# Assistant_Parameters.net
KiCad netlist of a schematic drawn in Altium Designer
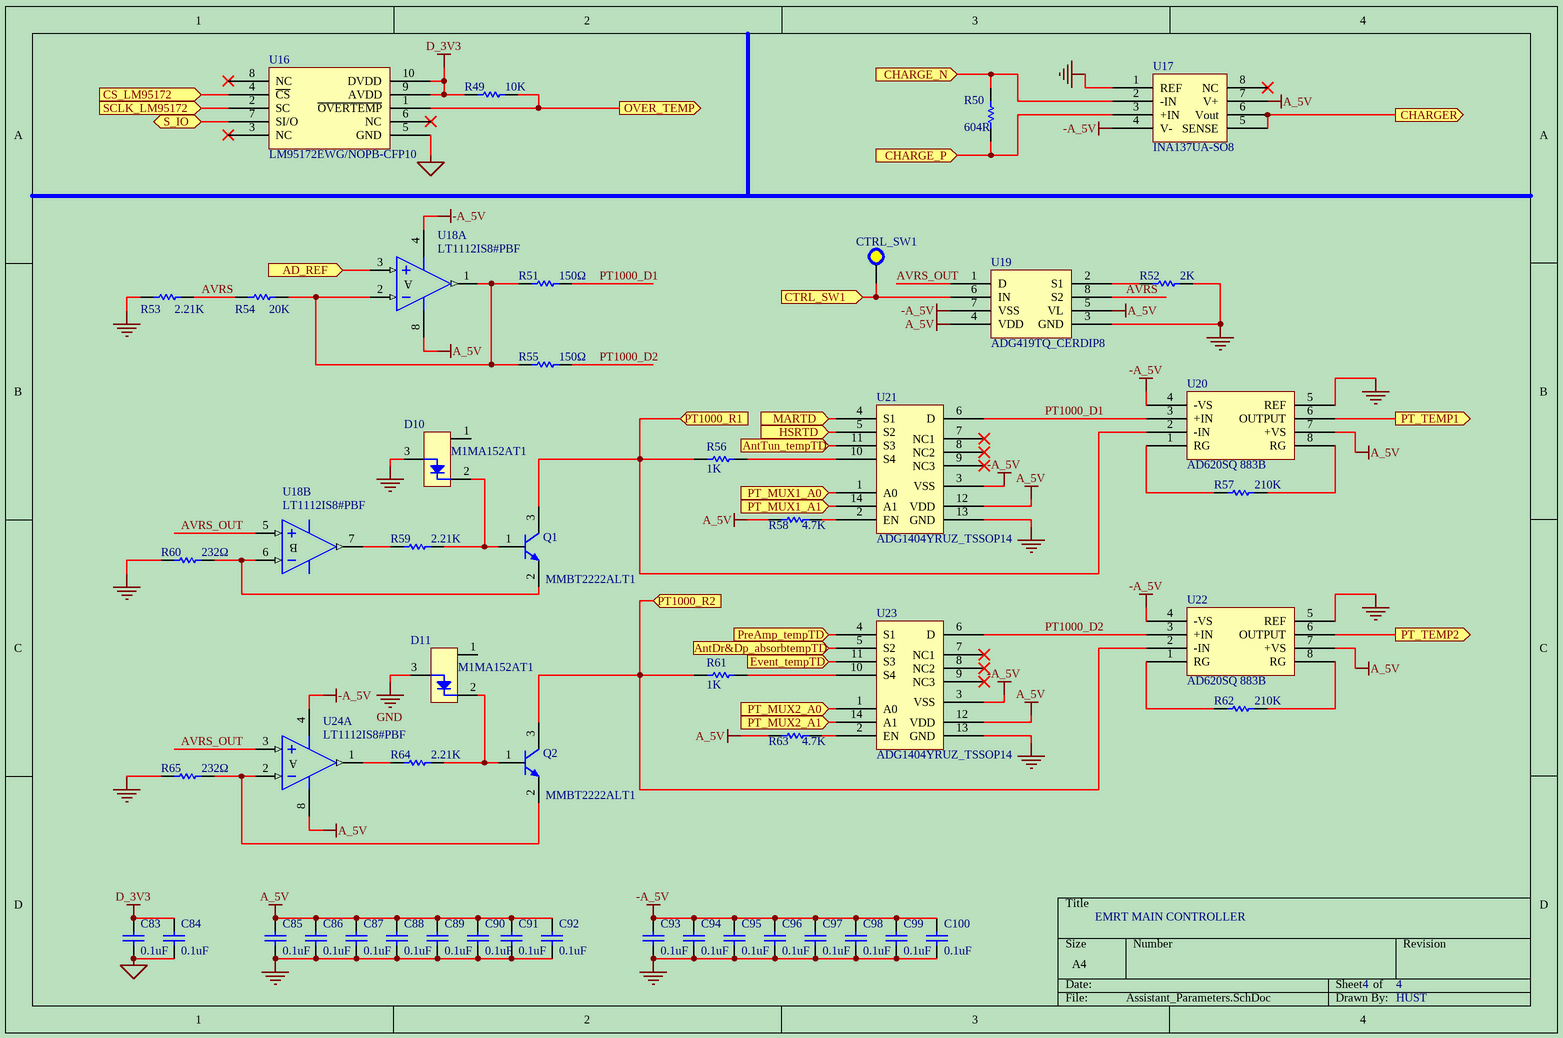
[diagram p0: Assistant_Parameters.SchDoc]

(export (version "E")
  (design (tool "Eeschema 10.0.6"))
  (components
    (comp (ref "C83")
      (value "0.1uF")
      (footprint "CAPS0805_57")
      (description "Capacitor")
      (fields (field (name "PART NUMBER") "Y20025084") (field (name "Comment") "Cap"))
      (libsource (lib "Cap") (part "Cap"))
    )
    (comp (ref "C84")
      (value "0.1uF")
      (footprint "CAPS0805_57")
      (description "Capacitor")
      (fields (field (name "PART NUMBER") "Y20025084") (field (name "Comment") "Cap"))
      (libsource (lib "Cap") (part "Cap"))
    )
    (comp (ref "C85")
      (value "0.1uF")
      (footprint "CAPS0805_57")
      (description "Capacitor")
      (fields (field (name "PART NUMBER") "Y20024100") (field (name "Comment") "Cap"))
      (libsource (lib "电容") (part "Y20024100"))
    )
    (comp (ref "C86")
      (value "Cap")
      (footprint "CAPS0805_57")
      (description "Capacitor")
      (fields (field (name "PART NUMBER") "Y20002409") (field (name "ALTIUM_UNNAMED_8") "0.1uF"))
      (libsource (lib "电容") (part "Y20002409"))
    )
    (comp (ref "C87")
      (value "0.1uF")
      (footprint "CAPS0805_57")
      (description "Capacitor")
      (fields (field (name "PART NUMBER") "Y20025084") (field (name "Comment") "Cap"))
      (libsource (lib "Cap") (part "Cap"))
    )
    (comp (ref "C88")
      (value "0.1uF")
      (footprint "CAPS0805_57")
      (description "Capacitor")
      (fields (field (name "PART NUMBER") "Y20024100") (field (name "Comment") "Cap"))
      (libsource (lib "电容") (part "Y20024100"))
    )
    (comp (ref "C89")
      (value "0.1uF")
      (footprint "CAPS0805_57")
      (description "Capacitor")
      (fields (field (name "PART NUMBER") "Y20024100") (field (name "Comment") "Cap"))
      (libsource (lib "电容") (part "Y20024100"))
    )
    (comp (ref "C90")
      (value "0.1uF")
      (footprint "CAPS0805_57")
      (description "Capacitor")
      (fields (field (name "PART NUMBER") "Y20024100") (field (name "Comment") "Cap"))
      (libsource (lib "电容") (part "Y20024100"))
    )
    (comp (ref "C91")
      (value "0.1uF")
      (footprint "CAPS0805_57")
      (description "Capacitor")
      (fields (field (name "PART NUMBER") "Y20024100") (field (name "Comment") "Cap"))
      (libsource (lib "电容") (part "Y20024100"))
    )
    (comp (ref "C92")
      (value "0.1uF")
      (footprint "CAPS0805_57")
      (description "Capacitor")
      (fields (field (name "PART NUMBER") "Y20024100") (field (name "Comment") "Cap"))
      (libsource (lib "电容") (part "Y20024100"))
    )
    (comp (ref "C93")
      (value "0.1uF")
      (footprint "CAPS0805_57")
      (description "Capacitor")
      (fields (field (name "PART NUMBER") "Y20025084") (field (name "Comment") "Cap"))
      (libsource (lib "Cap") (part "Cap"))
    )
    (comp (ref "C94")
      (value "Cap")
      (footprint "CAPS0805_57")
      (description "Capacitor")
      (fields (field (name "PART NUMBER") "Y20002409") (field (name "ALTIUM_UNNAMED_8") "0.1uF"))
      (libsource (lib "电容") (part "Y20002409"))
    )
    (comp (ref "C95")
      (value "0.1uF")
      (footprint "CAPS0805_57")
      (description "Capacitor")
      (fields (field (name "PART NUMBER") "Y20024100") (field (name "Comment") "Cap"))
      (libsource (lib "电容") (part "Y20024100"))
    )
    (comp (ref "C96")
      (value "0.1uF")
      (footprint "CAPS0805_57")
      (description "Capacitor")
      (fields (field (name "PART NUMBER") "Y20024100") (field (name "Comment") "Cap"))
      (libsource (lib "电容") (part "Y20024100"))
    )
    (comp (ref "C97")
      (value "0.1uF")
      (footprint "CAPS0805_57")
      (description "Capacitor")
      (fields (field (name "PART NUMBER") "Y20024100") (field (name "Comment") "Cap"))
      (libsource (lib "电容") (part "Y20024100"))
    )
    (comp (ref "C98")
      (value "0.1uF")
      (footprint "CAPS0805_57")
      (description "Capacitor")
      (fields (field (name "PART NUMBER") "Y20024100") (field (name "Comment") "Cap"))
      (libsource (lib "电容") (part "Y20024100"))
    )
    (comp (ref "C99")
      (value "0.1uF")
      (footprint "CAPS0805_57")
      (description "Capacitor")
      (fields (field (name "PART NUMBER") "Y20024100") (field (name "Comment") "Cap"))
      (libsource (lib "电容") (part "Y20024100"))
    )
    (comp (ref "C100")
      (value "0.1uF")
      (footprint "CAPS0805_57")
      (description "Capacitor")
      (fields (field (name "PART NUMBER") "Y20024100") (field (name "Comment") "Cap"))
      (libsource (lib "电容") (part "Y20024100"))
    )
    (comp (ref "CTRL_SW1")
      (value "TEST_SMALL")
      (footprint "test_small")
      (libsource (lib "srj") (part "TEST_SMALL"))
    )
    (comp (ref "D10")
      (value "M1MA152AT1")
      (footprint "SC-59")
      (fields (field (name "PART NUMBER") "Y20032999"))
      (libsource (lib "MC-HT") (part "M1MA152AT1"))
    )
    (comp (ref "D11")
      (value "M1MA152AT1")
      (footprint "SC-59")
      (fields (field (name "PART NUMBER") "Y20032999"))
      (libsource (lib "MC-HT") (part "M1MA152AT1"))
    )
    (comp (ref "Q1")
      (value "MMBT2222ALT1")
      (footprint "V-PDSO_3q290×240×100_p190")
      (description "General Purpose Transistor NPN Silicon")
      (libsource (lib "MC-HT") (part "MMBT2222ALT1"))
    )
    (comp (ref "Q2")
      (value "MMBT2222ALT1")
      (footprint "V-PDSO_3q290×240×100_p190")
      (description "General Purpose Transistor NPN Silicon")
      (libsource (lib "MC-HT") (part "MMBT2222ALT1"))
    )
    (comp (ref "R49")
      (value "10K")
      (footprint "RESS0805")
      (description "Semiconductor Resistor")
      (fields
        (field (name "MANUFACTURER") "Generic Components")
        (field (name "Comment") "Res")
        (field (name "PUBLISHER") "Altium Hobart Technology Centre")
      )
      (libsource (lib "EMRT MAIN CONTROLLER") (part "Res"))
    )
    (comp (ref "R50")
      (value "604R")
      (footprint "RESS0805")
      (description "Semiconductor Resistor")
      (fields
        (field (name "MANUFACTURER") "Generic Components")
        (field (name "Comment") "Res")
        (field (name "PUBLISHER") "Altium Hobart Technology Centre")
      )
      (libsource (lib "EMRT MAIN CONTROLLER") (part "Res"))
    )
    (comp (ref "R51")
      (value "150Ω")
      (footprint "RESS0805")
      (description "Semiconductor Resistor")
      (fields
        (field (name "MANUFACTURER") "Generic Components")
        (field (name "Comment") "Res")
        (field (name "PUBLISHER") "Altium Hobart Technology Centre")
      )
      (libsource (lib "EMRT MAIN CONTROLLER") (part "Res"))
    )
    (comp (ref "R52")
      (value "2K")
      (footprint "RESS0805")
      (description "Semiconductor Resistor")
      (fields
        (field (name "MANUFACTURER") "Generic Components")
        (field (name "Comment") "Res")
        (field (name "PUBLISHER") "Altium Hobart Technology Centre")
      )
      (libsource (lib "EMRT MAIN CONTROLLER") (part "Res"))
    )
    (comp (ref "R53")
      (value "2.21K")
      (footprint "RESS0805")
      (description "Semiconductor Resistor")
      (fields
        (field (name "MANUFACTURER") "Generic Components")
        (field (name "Comment") "Res")
        (field (name "PUBLISHER") "Altium Hobart Technology Centre")
      )
      (libsource (lib "EMRT MAIN CONTROLLER") (part "Res"))
    )
    (comp (ref "R54")
      (value "20K")
      (footprint "EMRT MAIN CONTROLLER:RESS0805")
      (description "Semiconductor Resistor")
      (fields
        (field (name "MANUFACTURER") "Generic Components")
        (field (name "Comment") "Res")
        (field (name "PUBLISHER") "Altium Hobart Technology Centre")
      )
      (libsource (lib "EMRT MAIN CONTROLLER") (part "Res"))
    )
    (comp (ref "R55")
      (value "150Ω")
      (footprint "RESS0805")
      (description "Semiconductor Resistor")
      (fields
        (field (name "MANUFACTURER") "Generic Components")
        (field (name "Comment") "Res")
        (field (name "PUBLISHER") "Altium Hobart Technology Centre")
      )
      (libsource (lib "EMRT MAIN CONTROLLER") (part "Res"))
    )
    (comp (ref "R56")
      (value "1K")
      (footprint "RESS0805")
      (description "Semiconductor Resistor")
      (fields
        (field (name "MANUFACTURER") "Generic Components")
        (field (name "Comment") "Res")
        (field (name "PUBLISHER") "Altium Hobart Technology Centre")
      )
      (libsource (lib "EMRT MAIN CONTROLLER") (part "Res"))
    )
    (comp (ref "R57")
      (value "210K")
      (footprint "RESS0805")
      (description "Semiconductor Resistor")
      (fields
        (field (name "MANUFACTURER") "Generic Components")
        (field (name "Comment") "Res")
        (field (name "PUBLISHER") "Altium Hobart Technology Centre")
      )
      (libsource (lib "EMRT MAIN CONTROLLER") (part "Res"))
    )
    (comp (ref "R58")
      (value "4.7K")
      (footprint "RESS0805")
      (description "Semiconductor Resistor")
      (fields
        (field (name "MANUFACTURER") "Generic Components")
        (field (name "Comment") "Res")
        (field (name "PUBLISHER") "Altium Hobart Technology Centre")
      )
      (libsource (lib "EMRT MAIN CONTROLLER") (part "Res"))
    )
    (comp (ref "R59")
      (value "2.21K")
      (footprint "RESS0805")
      (description "Semiconductor Resistor")
      (fields
        (field (name "MANUFACTURER") "Generic Components")
        (field (name "Comment") "Res")
        (field (name "PUBLISHER") "Altium Hobart Technology Centre")
      )
      (libsource (lib "EMRT MAIN CONTROLLER") (part "Res"))
    )
    (comp (ref "R60")
      (value "232Ω")
      (footprint "RESS0805")
      (description "Semiconductor Resistor")
      (fields
        (field (name "MANUFACTURER") "Generic Components")
        (field (name "Comment") "Res")
        (field (name "PUBLISHER") "Altium Hobart Technology Centre")
      )
      (libsource (lib "EMRT MAIN CONTROLLER") (part "Res"))
    )
    (comp (ref "R61")
      (value "1K")
      (footprint "RESS0805")
      (description "Semiconductor Resistor")
      (fields
        (field (name "MANUFACTURER") "Generic Components")
        (field (name "Comment") "Res")
        (field (name "PUBLISHER") "Altium Hobart Technology Centre")
      )
      (libsource (lib "EMRT MAIN CONTROLLER") (part "Res"))
    )
    (comp (ref "R62")
      (value "210K")
      (footprint "RESS0805")
      (description "Semiconductor Resistor")
      (fields
        (field (name "MANUFACTURER") "Generic Components")
        (field (name "Comment") "Res")
        (field (name "PUBLISHER") "Altium Hobart Technology Centre")
      )
      (libsource (lib "EMRT MAIN CONTROLLER") (part "Res"))
    )
    (comp (ref "R63")
      (value "4.7K")
      (footprint "RESS0805")
      (description "Semiconductor Resistor")
      (fields
        (field (name "MANUFACTURER") "Generic Components")
        (field (name "Comment") "Res")
        (field (name "PUBLISHER") "Altium Hobart Technology Centre")
      )
      (libsource (lib "EMRT MAIN CONTROLLER") (part "Res"))
    )
    (comp (ref "R64")
      (value "2.21K")
      (footprint "RESS0805")
      (description "Semiconductor Resistor")
      (fields
        (field (name "MANUFACTURER") "Generic Components")
        (field (name "Comment") "Res")
        (field (name "PUBLISHER") "Altium Hobart Technology Centre")
      )
      (libsource (lib "EMRT MAIN CONTROLLER") (part "Res"))
    )
    (comp (ref "R65")
      (value "232Ω")
      (footprint "RESS0805")
      (description "Semiconductor Resistor")
      (fields
        (field (name "MANUFACTURER") "Generic Components")
        (field (name "Comment") "Res")
        (field (name "PUBLISHER") "Altium Hobart Technology Centre")
      )
      (libsource (lib "EMRT MAIN CONTROLLER") (part "Res"))
    )
    (comp (ref "U16")
      (value "LM95172EWG/NOPB-CFP10")
      (footprint "SOP10")
      (libsource (lib "srj") (part "LM95172EWG/NOPB"))
    )
    (comp (ref "U17")
      (value "INA137UA-SO8")
      (footprint "PDSO_8q600×490×175_p127")
      (libsource (lib "srj") (part "INA137"))
    )
    (comp (ref "U18")
      (value "LT1112IS8#PBF")
      (footprint "PDSO_8q600×490×175_p127")
      (description "Precision, Single-Supply Dual Operational Amplifier")
      (libsource (lib "MC-HT") (part "LT1112IS8#PBF"))
    )
    (comp (ref "U19")
      (value "ADG419TQ_CERDIP8")
      (footprint "CDIP_8q405×305×200_d19_p100_i300")
      (libsource (lib "MC-HT") (part "ADG419TQ/883"))
    )
    (comp (ref "U20")
      (value "AD620SQ 883B")
      (footprint "CDIP_8q405×305×200_d19_p100_i300")
      (libsource (lib "MC-HT") (part "AD620"))
    )
    (comp (ref "U21")
      (value "ADG1404YRUZ_TSSOP14")
      (footprint "TSSOP14")
      (libsource (lib "srj") (part "ADG1404"))
    )
    (comp (ref "U22")
      (value "AD620SQ 883B")
      (footprint "CDIP_8q405×305×200_d19_p100_i300")
      (libsource (lib "MC-HT") (part "AD620"))
    )
    (comp (ref "U23")
      (value "ADG1404YRUZ_TSSOP14")
      (footprint "TSSOP14")
      (libsource (lib "srj") (part "ADG1404"))
    )
    (comp (ref "U24")
      (value "LT1112IS8#PBF")
      (footprint "PDSO_8q600×490×175_p127")
      (description "Precision, Single-Supply Dual Operational Amplifier")
      (libsource (lib "MC-HT") (part "LT1112IS8#PBF"))
    )
  )
  (nets
    (net (code "1") (name "-A_5V") (class "Default")
      (node (ref "C100") (pin "2") (pinfunction "2_2") (pintype "passive"))
      (node (ref "C93") (pin "2") (pinfunction "2_2") (pintype "passive"))
      (node (ref "C94") (pin "1") (pinfunction "1_1") (pintype "passive"))
      (node (ref "C95") (pin "2") (pinfunction "2_2") (pintype "passive"))
      (node (ref "C96") (pin "2") (pinfunction "2_2") (pintype "passive"))
      (node (ref "C97") (pin "2") (pinfunction "2_2") (pintype "passive"))
      (node (ref "C98") (pin "2") (pinfunction "2_2") (pintype "passive"))
      (node (ref "C99") (pin "2") (pinfunction "2_2") (pintype "passive"))
      (node (ref "U17") (pin "4") (pinfunction "V-_4") (pintype "passive"))
      (node (ref "U18") (pin "4") (pinfunction "V-_4") (pintype "power_in"))
      (node (ref "U19") (pin "7") (pinfunction "VSS_7") (pintype "passive"))
      (node (ref "U20") (pin "4") (pinfunction "-VS_4") (pintype "passive"))
      (node (ref "U21") (pin "3") (pinfunction "VSS_3") (pintype "passive"))
      (node (ref "U22") (pin "4") (pinfunction "-VS_4") (pintype "passive"))
      (node (ref "U23") (pin "3") (pinfunction "VSS_3") (pintype "passive"))
      (node (ref "U24") (pin "4") (pinfunction "V-_4") (pintype "power_in"))
    )
    (net (code "2") (name "/AD_REF") (class "Default")
      (node (ref "U18") (pin "3") (pinfunction "IN+_3") (pintype "input"))
    )
    (net (code "3") (name "/AVRS") (class "Default")
      (node (ref "R53") (pin "1") (pinfunction "1_1") (pintype "passive"))
      (node (ref "R54") (pin "2") (pinfunction "2_2") (pintype "passive"))
      (node (ref "U19") (pin "8") (pinfunction "S2_8") (pintype "passive"))
    )
    (net (code "4") (name "/AVRS_OUT") (class "Default")
      (node (ref "U18") (pin "5") (pinfunction "IN+_5") (pintype "input"))
      (node (ref "U19") (pin "1") (pinfunction "D_1") (pintype "passive"))
      (node (ref "U24") (pin "3") (pinfunction "IN+_3") (pintype "input"))
    )
    (net (code "5") (name "/AntDr&Dp_absorbtempTD") (class "Default")
      (node (ref "U23") (pin "5") (pinfunction "S2_5") (pintype "passive"))
    )
    (net (code "6") (name "/AntTun_tempTD") (class "Default")
      (node (ref "U21") (pin "11") (pinfunction "S3_11") (pintype "passive"))
    )
    (net (code "7") (name "/CHARGER") (class "Default")
      (node (ref "U17") (pin "5") (pinfunction "SENSE_5") (pintype "passive"))
      (node (ref "U17") (pin "6") (pinfunction "Vout_6") (pintype "passive"))
    )
    (net (code "8") (name "/CHARGE_N") (class "Default")
      (node (ref "R50") (pin "1") (pinfunction "1_1") (pintype "passive"))
      (node (ref "U17") (pin "2") (pinfunction "-IN_2") (pintype "passive"))
    )
    (net (code "9") (name "/CHARGE_P") (class "Default")
      (node (ref "R50") (pin "2") (pinfunction "2_2") (pintype "passive"))
      (node (ref "U17") (pin "3") (pinfunction "+IN_3") (pintype "passive"))
    )
    (net (code "10") (name "/CS_LM95172") (class "Default")
      (node (ref "U16") (pin "4") (pinfunction "~{CS}_4") (pintype "passive"))
    )
    (net (code "11") (name "/CTRL_SW1") (class "Default")
      (node (ref "CTRL_SW1") (pin "1") (pinfunction "1_1") (pintype "passive"))
      (node (ref "U19") (pin "6") (pinfunction "IN_6") (pintype "passive"))
    )
    (net (code "12") (name "/Event_tempTD") (class "Default")
      (node (ref "U23") (pin "11") (pinfunction "S3_11") (pintype "passive"))
    )
    (net (code "13") (name "/HSRTD") (class "Default")
      (node (ref "U21") (pin "5") (pinfunction "S2_5") (pintype "passive"))
    )
    (net (code "14") (name "/MARTD") (class "Default")
      (node (ref "U21") (pin "4") (pinfunction "S1_4") (pintype "passive"))
    )
    (net (code "15") (name "/OVER_TEMP") (class "Default")
      (node (ref "R49") (pin "1") (pinfunction "1_1") (pintype "passive"))
      (node (ref "U16") (pin "1") (pinfunction "~{OVERTEMP}_1") (pintype "passive"))
    )
    (net (code "16") (name "/PT1000_D1") (class "Default")
      (node (ref "R51") (pin "1") (pinfunction "1_1") (pintype "passive"))
      (node (ref "U20") (pin "3") (pinfunction "+IN_3") (pintype "passive"))
      (node (ref "U21") (pin "6") (pinfunction "D_6") (pintype "passive"))
    )
    (net (code "17") (name "/PT1000_D2") (class "Default")
      (node (ref "R55") (pin "1") (pinfunction "1_1") (pintype "passive"))
      (node (ref "U22") (pin "3") (pinfunction "+IN_3") (pintype "passive"))
      (node (ref "U23") (pin "6") (pinfunction "D_6") (pintype "passive"))
    )
    (net (code "18") (name "/PT1000_R1") (class "Default")
      (node (ref "Q1") (pin "3") (pinfunction "C_3") (pintype "passive"))
      (node (ref "R56") (pin "1") (pinfunction "1_1") (pintype "passive"))
      (node (ref "U20") (pin "2") (pinfunction "-IN_2") (pintype "passive"))
    )
    (net (code "19") (name "/PT1000_R2") (class "Default")
      (node (ref "Q2") (pin "3") (pinfunction "C_3") (pintype "passive"))
      (node (ref "R61") (pin "1") (pinfunction "1_1") (pintype "passive"))
      (node (ref "U22") (pin "2") (pinfunction "-IN_2") (pintype "passive"))
    )
    (net (code "20") (name "/PT_MUX1_A0") (class "Default")
      (node (ref "U21") (pin "1") (pinfunction "A0_1") (pintype "passive"))
    )
    (net (code "21") (name "/PT_MUX1_A1") (class "Default")
      (node (ref "U21") (pin "14") (pinfunction "A1_14") (pintype "passive"))
    )
    (net (code "22") (name "/PT_MUX2_A0") (class "Default")
      (node (ref "U23") (pin "1") (pinfunction "A0_1") (pintype "passive"))
    )
    (net (code "23") (name "/PT_MUX2_A1") (class "Default")
      (node (ref "U23") (pin "14") (pinfunction "A1_14") (pintype "passive"))
    )
    (net (code "24") (name "/PT_TEMP1") (class "Default")
      (node (ref "U20") (pin "6") (pinfunction "OUTPUT_6") (pintype "passive"))
    )
    (net (code "25") (name "/PT_TEMP2") (class "Default")
      (node (ref "U22") (pin "6") (pinfunction "OUTPUT_6") (pintype "passive"))
    )
    (net (code "26") (name "/PreAmp_tempTD") (class "Default")
      (node (ref "U23") (pin "4") (pinfunction "S1_4") (pintype "passive"))
    )
    (net (code "27") (name "/SCLK_LM95172") (class "Default")
      (node (ref "U16") (pin "2") (pinfunction "SC_2") (pintype "passive"))
    )
    (net (code "28") (name "/S_IO") (class "Default")
      (node (ref "U16") (pin "7") (pinfunction "SI/O_7") (pintype "passive"))
    )
    (net (code "29") (name "A_5V") (class "Default")
      (node (ref "C85") (pin "2") (pinfunction "2_2") (pintype "passive"))
      (node (ref "C86") (pin "1") (pinfunction "1_1") (pintype "passive"))
      (node (ref "C87") (pin "2") (pinfunction "2_2") (pintype "passive"))
      (node (ref "C88") (pin "1") (pinfunction "1_1") (pintype "passive"))
      (node (ref "C89") (pin "2") (pinfunction "2_2") (pintype "passive"))
      (node (ref "C90") (pin "2") (pinfunction "2_2") (pintype "passive"))
      (node (ref "C91") (pin "2") (pinfunction "2_2") (pintype "passive"))
      (node (ref "C92") (pin "2") (pinfunction "2_2") (pintype "passive"))
      (node (ref "R58") (pin "1") (pinfunction "1_1") (pintype "passive"))
      (node (ref "R63") (pin "1") (pinfunction "1_1") (pintype "passive"))
      (node (ref "U17") (pin "7") (pinfunction "V+_7") (pintype "passive"))
      (node (ref "U18") (pin "8") (pinfunction "V+_8") (pintype "power_in"))
      (node (ref "U19") (pin "4") (pinfunction "VDD_4") (pintype "passive"))
      (node (ref "U19") (pin "5") (pinfunction "VL_5") (pintype "passive"))
      (node (ref "U20") (pin "7") (pinfunction "+VS_7") (pintype "passive"))
      (node (ref "U21") (pin "12") (pinfunction "VDD_12") (pintype "passive"))
      (node (ref "U22") (pin "7") (pinfunction "+VS_7") (pintype "passive"))
      (node (ref "U23") (pin "12") (pinfunction "VDD_12") (pintype "passive"))
      (node (ref "U24") (pin "8") (pinfunction "V+_8") (pintype "power_in"))
    )
    (net (code "30") (name "DGND") (class "Default")
      (node (ref "C83") (pin "1") (pinfunction "1_1") (pintype "passive"))
      (node (ref "C84") (pin "1") (pinfunction "1_1") (pintype "passive"))
      (node (ref "U16") (pin "5") (pinfunction "GND_5") (pintype "passive"))
    )
    (net (code "31") (name "D_3V3") (class "Default")
      (node (ref "C83") (pin "2") (pinfunction "2_2") (pintype "passive"))
      (node (ref "C84") (pin "2") (pinfunction "2_2") (pintype "passive"))
      (node (ref "R49") (pin "2") (pinfunction "2_2") (pintype "passive"))
      (node (ref "U16") (pin "10") (pinfunction "DVDD_10") (pintype "power_in"))
      (node (ref "U16") (pin "9") (pinfunction "AVDD_9") (pintype "power_in"))
    )
    (net (code "32") (name "GND") (class "Default")
      (node (ref "C100") (pin "1") (pinfunction "1_1") (pintype "passive"))
      (node (ref "C85") (pin "1") (pinfunction "1_1") (pintype "passive"))
      (node (ref "C86") (pin "2") (pinfunction "2_2") (pintype "passive"))
      (node (ref "C87") (pin "1") (pinfunction "1_1") (pintype "passive"))
      (node (ref "C88") (pin "2") (pinfunction "2_2") (pintype "passive"))
      (node (ref "C89") (pin "1") (pinfunction "1_1") (pintype "passive"))
      (node (ref "C90") (pin "1") (pinfunction "1_1") (pintype "passive"))
      (node (ref "C91") (pin "1") (pinfunction "1_1") (pintype "passive"))
      (node (ref "C92") (pin "1") (pinfunction "1_1") (pintype "passive"))
      (node (ref "C93") (pin "1") (pinfunction "1_1") (pintype "passive"))
      (node (ref "C94") (pin "2") (pinfunction "2_2") (pintype "passive"))
      (node (ref "C95") (pin "1") (pinfunction "1_1") (pintype "passive"))
      (node (ref "C96") (pin "1") (pinfunction "1_1") (pintype "passive"))
      (node (ref "C97") (pin "1") (pinfunction "1_1") (pintype "passive"))
      (node (ref "C98") (pin "1") (pinfunction "1_1") (pintype "passive"))
      (node (ref "C99") (pin "1") (pinfunction "1_1") (pintype "passive"))
      (node (ref "D10") (pin "3") (pintype "passive"))
      (node (ref "D11") (pin "3") (pintype "passive"))
      (node (ref "R52") (pin "1") (pinfunction "1_1") (pintype "passive"))
      (node (ref "R53") (pin "2") (pinfunction "2_2") (pintype "passive"))
      (node (ref "R60") (pin "2") (pinfunction "2_2") (pintype "passive"))
      (node (ref "R65") (pin "2") (pinfunction "2_2") (pintype "passive"))
      (node (ref "U17") (pin "1") (pinfunction "REF_1") (pintype "passive"))
      (node (ref "U19") (pin "3") (pinfunction "GND_3") (pintype "passive"))
      (node (ref "U20") (pin "5") (pinfunction "REF_5") (pintype "passive"))
      (node (ref "U21") (pin "13") (pinfunction "GND_13") (pintype "passive"))
      (node (ref "U22") (pin "5") (pinfunction "REF_5") (pintype "passive"))
      (node (ref "U23") (pin "13") (pinfunction "GND_13") (pintype "passive"))
    )
    (net (code "33") (name "Net-(Q1-B)") (class "Default")
      (node (ref "D10") (pin "2") (pintype "passive"))
      (node (ref "Q1") (pin "1") (pinfunction "B_1") (pintype "passive"))
      (node (ref "R59") (pin "1") (pinfunction "1_1") (pintype "passive"))
    )
    (net (code "34") (name "Net-(Q1-E)") (class "Default")
      (node (ref "Q1") (pin "2") (pinfunction "E_2") (pintype "passive"))
      (node (ref "R60") (pin "1") (pinfunction "1_1") (pintype "passive"))
      (node (ref "U18") (pin "6") (pinfunction "IN-_6") (pintype "input"))
    )
    (net (code "35") (name "Net-(Q2-B)") (class "Default")
      (node (ref "D11") (pin "2") (pintype "passive"))
      (node (ref "Q2") (pin "1") (pinfunction "B_1") (pintype "passive"))
      (node (ref "R64") (pin "1") (pinfunction "1_1") (pintype "passive"))
    )
    (net (code "36") (name "Net-(Q2-E)") (class "Default")
      (node (ref "Q2") (pin "2") (pinfunction "E_2") (pintype "passive"))
      (node (ref "R65") (pin "1") (pinfunction "1_1") (pintype "passive"))
      (node (ref "U24") (pin "2") (pinfunction "IN-_2") (pintype "input"))
    )
    (net (code "37") (name "Net-(R57-Pad1)") (class "Default")
      (node (ref "R57") (pin "1") (pinfunction "1_1") (pintype "passive"))
      (node (ref "U20") (pin "8") (pinfunction "RG_8") (pintype "passive"))
    )
    (net (code "38") (name "Net-(R57-Pad2)") (class "Default")
      (node (ref "R57") (pin "2") (pinfunction "2_2") (pintype "passive"))
      (node (ref "U20") (pin "1") (pinfunction "RG_1") (pintype "passive"))
    )
    (net (code "39") (name "Net-(R62-Pad1)") (class "Default")
      (node (ref "R62") (pin "1") (pinfunction "1_1") (pintype "passive"))
      (node (ref "U22") (pin "8") (pinfunction "RG_8") (pintype "passive"))
    )
    (net (code "40") (name "Net-(R62-Pad2)") (class "Default")
      (node (ref "R62") (pin "2") (pinfunction "2_2") (pintype "passive"))
      (node (ref "U22") (pin "1") (pinfunction "RG_1") (pintype "passive"))
    )
    (net (code "41") (name "Net-(U18A-IN-)") (class "Default")
      (node (ref "R51") (pin "2") (pinfunction "2_2") (pintype "passive"))
      (node (ref "R54") (pin "1") (pinfunction "1_1") (pintype "passive"))
      (node (ref "R55") (pin "2") (pinfunction "2_2") (pintype "passive"))
      (node (ref "U18") (pin "1") (pinfunction "OUT_1") (pintype "output"))
      (node (ref "U18") (pin "2") (pinfunction "IN-_2") (pintype "input"))
    )
    (net (code "42") (name "Net-(U18B-OUT)") (class "Default")
      (node (ref "R59") (pin "2") (pinfunction "2_2") (pintype "passive"))
      (node (ref "U18") (pin "7") (pinfunction "OUT_7") (pintype "output"))
    )
    (net (code "43") (name "Net-(U19-S1)") (class "Default")
      (node (ref "R52") (pin "2") (pinfunction "2_2") (pintype "passive"))
      (node (ref "U19") (pin "2") (pinfunction "S1_2") (pintype "passive"))
    )
    (net (code "44") (name "Net-(U21-EN)") (class "Default")
      (node (ref "R58") (pin "2") (pinfunction "2_2") (pintype "passive"))
      (node (ref "U21") (pin "2") (pinfunction "EN_2") (pintype "passive"))
    )
    (net (code "45") (name "Net-(U21-S4)") (class "Default")
      (node (ref "R56") (pin "2") (pinfunction "2_2") (pintype "passive"))
      (node (ref "U21") (pin "10") (pinfunction "S4_10") (pintype "passive"))
    )
    (net (code "46") (name "Net-(U23-EN)") (class "Default")
      (node (ref "R63") (pin "2") (pinfunction "2_2") (pintype "passive"))
      (node (ref "U23") (pin "2") (pinfunction "EN_2") (pintype "passive"))
    )
    (net (code "47") (name "Net-(U23-S4)") (class "Default")
      (node (ref "R61") (pin "2") (pinfunction "2_2") (pintype "passive"))
      (node (ref "U23") (pin "10") (pinfunction "S4_10") (pintype "passive"))
    )
    (net (code "48") (name "Net-(U24A-OUT)") (class "Default")
      (node (ref "R64") (pin "2") (pinfunction "2_2") (pintype "passive"))
      (node (ref "U24") (pin "1") (pinfunction "OUT_1") (pintype "output"))
    )
    (net (code "49") (name "unconnected-(D10-Pad1)") (class "Default")
      (node (ref "D10") (pin "1") (pintype "passive"))
    )
    (net (code "50") (name "unconnected-(D11-Pad1)") (class "Default")
      (node (ref "D11") (pin "1") (pintype "passive"))
    )
    (net (code "51") (name "unconnected-(U16-NC-Pad3)") (class "Default")
      (node (ref "U16") (pin "3") (pinfunction "NC_3") (pintype "passive+no_connect"))
    )
    (net (code "52") (name "unconnected-(U16-NC-Pad6)") (class "Default")
      (node (ref "U16") (pin "6") (pinfunction "NC_6") (pintype "passive+no_connect"))
    )
    (net (code "53") (name "unconnected-(U16-NC-Pad8)") (class "Default")
      (node (ref "U16") (pin "8") (pinfunction "NC_8") (pintype "passive+no_connect"))
    )
    (net (code "54") (name "unconnected-(U17-NC-Pad8)") (class "Default")
      (node (ref "U17") (pin "8") (pinfunction "NC_8") (pintype "passive+no_connect"))
    )
    (net (code "55") (name "unconnected-(U21-NC1-Pad7)") (class "Default")
      (node (ref "U21") (pin "7") (pinfunction "NC1_7") (pintype "passive+no_connect"))
    )
    (net (code "56") (name "unconnected-(U21-NC2-Pad8)") (class "Default")
      (node (ref "U21") (pin "8") (pinfunction "NC2_8") (pintype "passive+no_connect"))
    )
    (net (code "57") (name "unconnected-(U21-NC3-Pad9)") (class "Default")
      (node (ref "U21") (pin "9") (pinfunction "NC3_9") (pintype "passive+no_connect"))
    )
    (net (code "58") (name "unconnected-(U23-NC1-Pad7)") (class "Default")
      (node (ref "U23") (pin "7") (pinfunction "NC1_7") (pintype "passive+no_connect"))
    )
    (net (code "59") (name "unconnected-(U23-NC2-Pad8)") (class "Default")
      (node (ref "U23") (pin "8") (pinfunction "NC2_8") (pintype "passive+no_connect"))
    )
    (net (code "60") (name "unconnected-(U23-NC3-Pad9)") (class "Default")
      (node (ref "U23") (pin "9") (pinfunction "NC3_9") (pintype "passive+no_connect"))
    )
  )
)
